# CT.net
KiCad netlist of a schematic drawn in Altium Designer
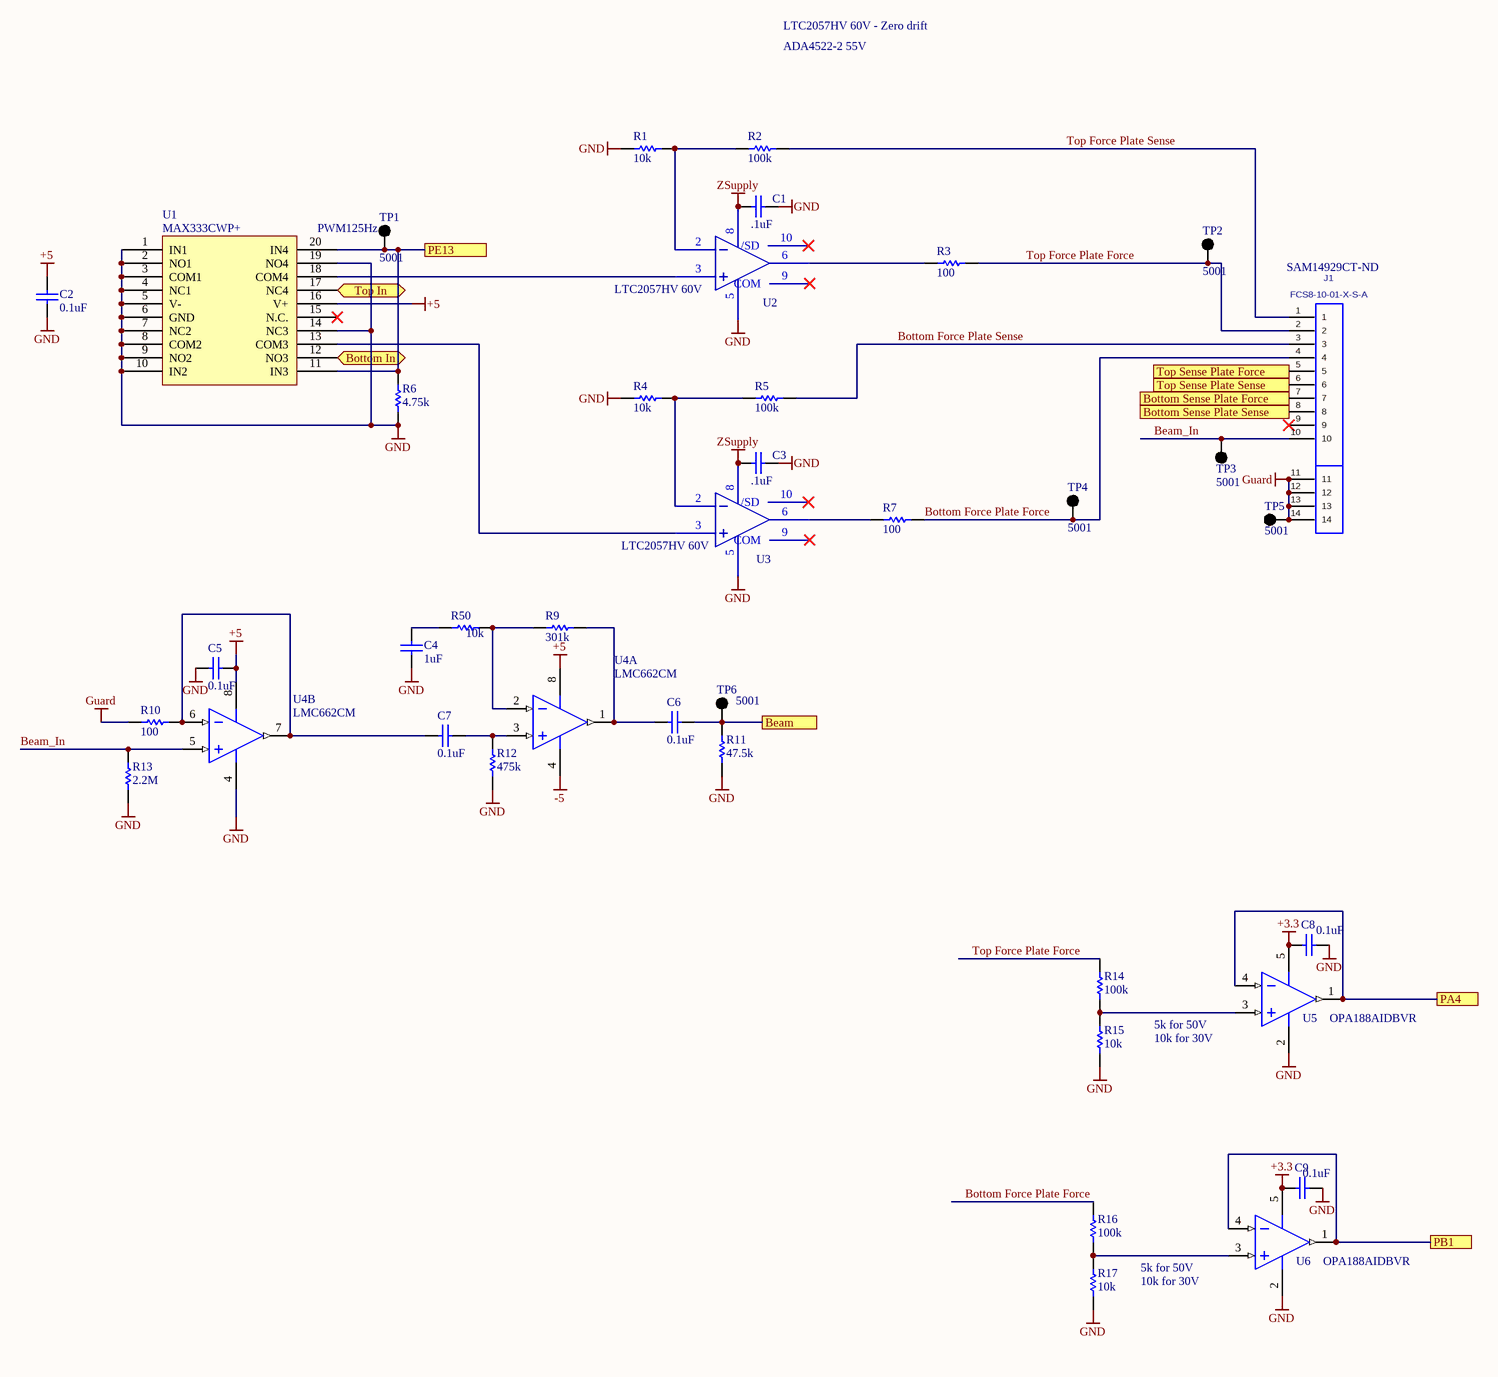
[diagram p0: CT.SchDoc]

(export (version "E")
  (design (tool "Eeschema 10.0.6"))
  (components
    (comp (ref "C1")
      (value ".1uF")
      (footprint "CAPC0805(2012)75_M")
      (description "0.1µF ±10% 16V Ceramic Capacitor X7R 0805 (2012 Metric)")
      (fields
        (field (name "MANUFACTURER") "Yageo")
        (field (name "MANUFACTURER PART NUMBER") "CC0805KRX7R7BB104")
      )
      (libsource (lib "Altium Content Vault") (part "CMP-1036-01414-1"))
    )
    (comp (ref "C2")
      (value "0.1uF")
      (footprint "CAPC0402(1005)60_L")
      (description "CAP CER 0.1UF 10V X7R 0402")
      (fields
        (field (name "MANUFACTURER") "Murata Electronics North America")
        (field (name "MANUFACTURER PART NUMBER") "GRM155R71A104KA01D")
      )
      (libsource (lib "Altium Content Vault") (part "CMP-1034-00252-1"))
    )
    (comp (ref "C3")
      (value ".1uF")
      (footprint "CAPC0805(2012)75_M")
      (description "0.1µF ±10% 16V Ceramic Capacitor X7R 0805 (2012 Metric)")
      (fields
        (field (name "MANUFACTURER") "Yageo")
        (field (name "MANUFACTURER PART NUMBER") "CC0805KRX7R7BB104")
      )
      (libsource (lib "Altium Content Vault") (part "CMP-1036-01414-1"))
    )
    (comp (ref "C4")
      (value "1uF")
      (footprint "CAPC0402(1005)60_L")
      (description "1µF ±10% 16V Ceramic Capacitor X5R 0402 (1005 Metric)")
      (fields
        (field (name "MANUFACTURER") "Samsung")
        (field (name "MANUFACTURER PART NUMBER") "CL05A105KO5NNNC")
      )
      (libsource (lib "Altium Content Vault") (part "CMP-1034-00252-1"))
    )
    (comp (ref "C5")
      (value "0.1uF")
      (footprint "CAPC0402(1005)60_L")
      (description "CAP CER 0.1UF 10V X7R 0402")
      (fields
        (field (name "MANUFACTURER") "Murata Electronics North America")
        (field (name "MANUFACTURER PART NUMBER") "GRM155R71A104KA01D")
      )
      (libsource (lib "Altium Content Vault") (part "CMP-1034-00252-1"))
    )
    (comp (ref "C6")
      (value "0.1uF")
      (footprint "CAPC0402(1005)60_L")
      (description "CAP CER 0.1UF 10V X7R 0402")
      (fields
        (field (name "MANUFACTURER") "Murata Electronics North America")
        (field (name "MANUFACTURER PART NUMBER") "GRM155R71A104KA01D")
      )
      (libsource (lib "Altium Content Vault") (part "CMP-1034-00252-1"))
    )
    (comp (ref "C7")
      (value "0.1uF")
      (footprint "CAPC0402(1005)60_L")
      (description "CAP CER 0.1UF 10V X7R 0402")
      (fields
        (field (name "MANUFACTURER") "Murata Electronics North America")
        (field (name "MANUFACTURER PART NUMBER") "GRM155R71A104KA01D")
      )
      (libsource (lib "Altium Content Vault") (part "CMP-1034-00252-1"))
    )
    (comp (ref "C8")
      (value "0.1uF")
      (footprint "CAPC0402(1005)60_L")
      (description "CAP CER 0.1UF 10V X7R 0402")
      (fields
        (field (name "MANUFACTURER") "Murata Electronics North America")
        (field (name "MANUFACTURER PART NUMBER") "GRM155R71A104KA01D")
      )
      (libsource (lib "Altium Content Vault") (part "CMP-1034-00252-1"))
    )
    (comp (ref "C9")
      (value "0.1uF")
      (footprint "CAPC0402(1005)60_L")
      (description "CAP CER 0.1UF 10V X7R 0402")
      (fields
        (field (name "MANUFACTURER") "Murata Electronics North America")
        (field (name "MANUFACTURER PART NUMBER") "GRM155R71A104KA01D")
      )
      (libsource (lib "Altium Content Vault") (part "CMP-1034-00252-1"))
    )
    (comp (ref "J1")
      (value "FCS8-10-01-X-S-A")
      (footprint "FCS8-10-01-X-S-A")
      (description "FCS8 Socket Assembly, 20-Pins, w/ Alignment Pins")
      (fields
        (field (name "SUPPLIER PART NUMBER 1") "SAM14929CT-ND")
        (field (name "MANUFACTURER") "Samtec")
        (field (name "MANUFACTURER PART NUMBER") "FCS8-10-01-L-S-A-TR")
        (field (name "CREATED") "31 NOV 2013 - WENDY XIN")
      )
      (libsource (lib "FCS8-10-01-X-S-A") (part "FCS8-10-01-X-S-A"))
    )
    (comp (ref "R1")
      (value "10k")
      (footprint "RESC0402(1005)_M")
      (description "10k 0.063W 1% 0402 (1005 Metric)  SMD")
      (fields
        (field (name "MANUFACTURER") "Panasonic")
        (field (name "MANUFACTURER PART NUMBER") "ERJ-2RKF1002X")
      )
      (libsource (lib "Altium Content Vault") (part "RES"))
    )
    (comp (ref "R2")
      (value "100k")
      (footprint "RESC0402(1005)_M")
      (description "100k 0.063W 1% 0402 (1005 Metric)  SMD")
      (fields
        (field (name "MANUFACTURER") "Panasonic")
        (field (name "MANUFACTURER PART NUMBER") "ERJ-2RKF1003X")
      )
      (libsource (lib "Altium Content Vault") (part "RES"))
    )
    (comp (ref "R3")
      (value "100")
      (footprint "RESC0402(1005)_N")
      (description "RES SMD 100 OHM 1% 1/16W 0402")
      (fields (field (name "TOLERANCE") "1 %") (field (name "POWER") "0.063 W"))
      (libsource (lib "Altium Content Vault") (part "RES"))
    )
    (comp (ref "R4")
      (value "10k")
      (footprint "RESC0402(1005)_M")
      (description "10k 0.063W 1% 0402 (1005 Metric)  SMD")
      (fields
        (field (name "MANUFACTURER") "Panasonic")
        (field (name "MANUFACTURER PART NUMBER") "ERJ-2RKF1002X")
      )
      (libsource (lib "Altium Content Vault") (part "RES"))
    )
    (comp (ref "R5")
      (value "100k")
      (footprint "RESC0402(1005)_M")
      (description "100k 0.063W 1% 0402 (1005 Metric)  SMD")
      (fields
        (field (name "MANUFACTURER") "Panasonic")
        (field (name "MANUFACTURER PART NUMBER") "ERJ-2RKF1003X")
      )
      (libsource (lib "Altium Content Vault") (part "RES"))
    )
    (comp (ref "R6")
      (value "4.75k")
      (footprint "RESC1005X40X25ML05T05")
      (description "Chip Resistor, 4.75 KOhm, +/- 1%, 100 mW, -55 to 155 degC, 0402 (1005 Metric), RoHS, Tape and Reel")
      (fields (field (name "PARTNUMBER") "ERJ-2RKF4751X") (field (name "MANUFACTURER") "Basic Passives"))
      (libsource (lib "Altium Content Vault") (part "RES-2"))
    )
    (comp (ref "R7")
      (value "100")
      (footprint "RESC0402(1005)_N")
      (description "RES SMD 100 OHM 1% 1/16W 0402")
      (fields (field (name "TOLERANCE") "1 %") (field (name "POWER") "0.063 W"))
      (libsource (lib "Altium Content Vault") (part "RES"))
    )
    (comp (ref "R9")
      (value "301k")
      (footprint "RESC0402(1005)_M")
      (description "RES SMD 301K OHM 1% 1/10W 0402")
      (fields
        (field (name "MANUFACTURER") "Panasonic")
        (field (name "MANUFACTURER PART NUMBER") "ERJ-2RKF3013X")
      )
      (libsource (lib "Altium Content Vault") (part "CMP-1011-00463-1"))
    )
    (comp (ref "R10")
      (value "100")
      (footprint "RESC0402(1005)_M")
      (description "6M34 0.063W 1% 0402 (1005 Metric)  SMD")
      (fields
        (field (name "MANUFACTURER") "Panasonic")
        (field (name "MANUFACTURER PART NUMBER") "ERJ-2RKF1000X")
      )
      (libsource (lib "Altium Content Vault") (part "RES"))
    )
    (comp (ref "R11")
      (value "47.5k")
      (footprint "RESC1005X40X25NL05T05")
      (description "RESISTOR, 0402, 47K5 1%, 0.1W")
      (fields (field (name "PART NUMBER") "ERJ-2RKF4752X") (field (name "MANUFACTURER") "Panasonic"))
      (libsource (lib "Altium Content Vault") (part "RES"))
    )
    (comp (ref "R12")
      (value "475k")
      (footprint "RESC1005X40X25LL05T05")
      (description "Resistor 0402 Case 475k 1% 0.1W 100ppm/C")
      (fields (field (name "PART NUMBER") "ERJ-2RKF4753X") (field (name "MANUFACTURER") "Panasonic"))
      (libsource (lib "Altium Content Vault") (part "RES"))
    )
    (comp (ref "R13")
      (value "2.2M")
      (footprint "RESC1005X40X25ML05T10")
      (description "RESISTOR, 0402 2M2 1%, REEL 10000")
      (fields (field (name "PART NUMBER") "RC0402FR-072M2L") (field (name "MANUFACTURER") "Yageo / Phycomp"))
      (libsource (lib "Altium Content Vault") (part "RES"))
    )
    (comp (ref "R14")
      (value "100k")
      (footprint "RESC0402(1005)_M")
      (description "100k 0.063W 1% 0402 (1005 Metric)  SMD")
      (fields
        (field (name "MANUFACTURER") "Panasonic")
        (field (name "MANUFACTURER PART NUMBER") "ERJ-2RKF1003X")
      )
      (libsource (lib "Altium Content Vault") (part "RES"))
    )
    (comp (ref "R15")
      (value "10k")
      (footprint "RESC0402(1005)_M")
      (description "10k 0.063W 1% 0402 (1005 Metric)  SMD")
      (fields
        (field (name "MANUFACTURER") "Panasonic")
        (field (name "MANUFACTURER PART NUMBER") "ERJ-2RKF1002X")
      )
      (libsource (lib "Altium Content Vault") (part "RES"))
    )
    (comp (ref "R16")
      (value "100k")
      (footprint "RESC0402(1005)_M")
      (description "100k 0.063W 1% 0402 (1005 Metric)  SMD")
      (fields
        (field (name "MANUFACTURER") "Panasonic")
        (field (name "MANUFACTURER PART NUMBER") "ERJ-2RKF1003X")
      )
      (libsource (lib "Altium Content Vault") (part "RES"))
    )
    (comp (ref "R17")
      (value "10k")
      (footprint "RESC0402(1005)_M")
      (description "10k 0.063W 1% 0402 (1005 Metric)  SMD")
      (fields
        (field (name "MANUFACTURER") "Panasonic")
        (field (name "MANUFACTURER PART NUMBER") "ERJ-2RKF1002X")
      )
      (libsource (lib "Altium Content Vault") (part "RES"))
    )
    (comp (ref "R50")
      (value "10k")
      (footprint "RESC0402(1005)_M")
      (description "10k 0.063W 1% 0402 (1005 Metric)  SMD")
      (fields
        (field (name "MANUFACTURER") "Panasonic")
        (field (name "MANUFACTURER PART NUMBER") "ERJ-2RKF1002X")
      )
      (libsource (lib "Altium Content Vault") (part "RES"))
    )
    (comp (ref "TP1")
      (value "5001")
      (footprint "KSTN-5001")
      (description "Test Point, Black, 1-Pin THD, RoHS, Bulk")
      (fields (field (name "MANUFACTURER") "Keystone"))
      (libsource (lib "Altium Content Vault") (part "KSTN-TP-5001"))
    )
    (comp (ref "TP2")
      (value "5001")
      (footprint "KSTN-5001")
      (description "Test Point, Black, 1-Pin THD, RoHS, Bulk")
      (fields (field (name "MANUFACTURER") "Keystone"))
      (libsource (lib "Altium Content Vault") (part "KSTN-TP-5001"))
    )
    (comp (ref "TP3")
      (value "5001")
      (footprint "KSTN-5001")
      (description "Test Point, Black, 1-Pin THD, RoHS, Bulk")
      (fields (field (name "MANUFACTURER") "Keystone"))
      (libsource (lib "Altium Content Vault") (part "KSTN-TP-5001"))
    )
    (comp (ref "TP4")
      (value "5001")
      (footprint "KSTN-5001")
      (description "Test Point, Black, 1-Pin THD, RoHS, Bulk")
      (fields (field (name "MANUFACTURER") "Keystone"))
      (libsource (lib "Altium Content Vault") (part "KSTN-TP-5001"))
    )
    (comp (ref "TP5")
      (value "5001")
      (footprint "KSTN-5001")
      (description "Test Point, Black, 1-Pin THD, RoHS, Bulk")
      (fields (field (name "MANUFACTURER") "Keystone"))
      (libsource (lib "Altium Content Vault") (part "KSTN-TP-5001"))
    )
    (comp (ref "TP6")
      (value "5001")
      (footprint "KSTN-5001")
      (description "Test Point, Black, 1-Pin THD, RoHS, Bulk")
      (fields (field (name "MANUFACTURER") "Keystone"))
      (libsource (lib "Altium Content Vault") (part "KSTN-TP-5001"))
    )
    (comp (ref "U1")
      (value "MAX333CWP+")
      (footprint "TSOP65P640X90-20N")
      (description "IC SWITCH QUAD SPDT 20TSSOP")
      (fields (field (name "MANUFACTURER") "Maxim") (field (name "MANUFACTURER PART NUMBER") "MAX333AEUP+"))
      (libsource (lib "ZLS_Schematic_lib") (part "MAX333CWP+"))
    )
    (comp (ref "U2")
      (value "LTC2057HV 60V")
      (description "IC OPAMP ZRO-DRFT 1.5MHZ 10MSOP")
      (fields
        (field (name "MANUFACTURER") "Analog Devices / Linear Technology")
        (field (name "MANUFACTURER PART NUMBER") "LTC2057HVHMS#PBF")
      )
      (libsource (lib "ZLS_Schematic_lib") (part "LTC2057HV 60V"))
    )
    (comp (ref "U3")
      (value "LTC2057HV 60V")
      (description "IC OPAMP ZRO-DRFT 1.5MHZ 10MSOP")
      (fields
        (field (name "MANUFACTURER") "Analog Devices / Linear Technology")
        (field (name "MANUFACTURER PART NUMBER") "LTC2057HVHMS#PBF")
      )
      (libsource (lib "ZLS_Schematic_lib") (part "LTC2057HV 60V"))
    )
    (comp (ref "U4")
      (value "LMC662CM")
      (footprint "D0008A_M")
      (description "CMOS Dual Operational Amplifier, 8-pin Narrow SOIC")
      (fields (field (name "MANUFACTURER") "Texas Instruments"))
      (libsource (lib "Altium Content Vault") (part "AMP-OPA-LF353-8"))
    )
    (comp (ref "U5")
      (value "OPA188AIDBVR")
      (footprint "DBV0005A_M")
      (fields (field (name "MANUFACTURER") "Texas Instruments"))
      (libsource (lib "Altium Content Vault") (part "CMP-0809-00005-2"))
    )
    (comp (ref "U6")
      (value "OPA188AIDBVR")
      (footprint "DBV0005A_M")
      (fields (field (name "MANUFACTURER") "Texas Instruments"))
      (libsource (lib "Altium Content Vault") (part "CMP-0809-00005-2"))
    )
  )
  (nets
    (net (code "1") (name "+3.3") (class "Default")
      (node (ref "C8") (pin "2") (pinfunction "2_2") (pintype "passive"))
      (node (ref "C9") (pin "2") (pinfunction "2_2") (pintype "passive"))
      (node (ref "U5") (pin "5") (pinfunction "V+_5") (pintype "power_in"))
      (node (ref "U6") (pin "5") (pinfunction "V+_5") (pintype "power_in"))
    )
    (net (code "2") (name "+5") (class "Default")
      (node (ref "C2") (pin "2") (pinfunction "2_2") (pintype "passive"))
      (node (ref "C5") (pin "2") (pinfunction "2_2") (pintype "passive"))
      (node (ref "U1") (pin "16") (pinfunction "V+_16") (pintype "power_in"))
      (node (ref "U4") (pin "8") (pinfunction "V+_8") (pintype "power_in"))
    )
    (net (code "3") (name "-5") (class "Default")
      (node (ref "U4") (pin "4") (pinfunction "V-_4") (pintype "power_in"))
    )
    (net (code "4") (name "/Beam") (class "Default")
      (node (ref "C6") (pin "2") (pinfunction "2_2") (pintype "passive"))
      (node (ref "R11") (pin "2") (pinfunction "2_2") (pintype "passive"))
      (node (ref "TP6") (pin "1") (pintype "passive"))
    )
    (net (code "5") (name "/Beam_In") (class "Default")
      (node (ref "J1") (pin "10") (pinfunction "10_10") (pintype "passive"))
      (node (ref "R13") (pin "2") (pinfunction "2_2") (pintype "passive"))
      (node (ref "TP3") (pin "1") (pintype "passive"))
      (node (ref "U4") (pin "5") (pinfunction "INB+_5") (pintype "input"))
    )
    (net (code "6") (name "/Bottom Force Plate Force") (class "Default")
      (node (ref "J1") (pin "4") (pinfunction "4_4") (pintype "passive"))
      (node (ref "R16") (pin "2") (pinfunction "2_2") (pintype "passive"))
      (node (ref "R7") (pin "2") (pinfunction "2_2") (pintype "passive"))
      (node (ref "TP4") (pin "1") (pintype "passive"))
    )
    (net (code "7") (name "/Bottom Force Plate Sense") (class "Default")
      (node (ref "J1") (pin "3") (pinfunction "3_3") (pintype "passive"))
      (node (ref "R5") (pin "2") (pinfunction "2_2") (pintype "passive"))
    )
    (net (code "8") (name "/Bottom In") (class "Default")
      (node (ref "U1") (pin "12") (pinfunction "NO3_12") (pintype "passive"))
    )
    (net (code "9") (name "/Bottom Sense Plate Force") (class "Default")
      (node (ref "J1") (pin "7") (pinfunction "7_7") (pintype "passive"))
    )
    (net (code "10") (name "/Bottom Sense Plate Sense") (class "Default")
      (node (ref "J1") (pin "8") (pinfunction "8_8") (pintype "passive"))
    )
    (net (code "11") (name "/PA4") (class "Default")
      (node (ref "U5") (pin "1") (pinfunction "OUT_1") (pintype "output"))
      (node (ref "U5") (pin "4") (pinfunction "IN-_4") (pintype "input"))
    )
    (net (code "12") (name "/PB1") (class "Default")
      (node (ref "U6") (pin "1") (pinfunction "OUT_1") (pintype "output"))
      (node (ref "U6") (pin "4") (pinfunction "IN-_4") (pintype "input"))
    )
    (net (code "13") (name "/PE13") (class "Default")
      (node (ref "R6") (pin "2") (pinfunction "2_2") (pintype "passive"))
      (node (ref "TP1") (pin "1") (pintype "passive"))
      (node (ref "U1") (pin "11") (pinfunction "IN3_11") (pintype "passive"))
      (node (ref "U1") (pin "20") (pinfunction "IN4_20") (pintype "passive"))
    )
    (net (code "14") (name "/Top Force Plate Force") (class "Default")
      (node (ref "J1") (pin "2") (pinfunction "2_2") (pintype "passive"))
      (node (ref "R14") (pin "2") (pinfunction "2_2") (pintype "passive"))
      (node (ref "R3") (pin "2") (pinfunction "2_2") (pintype "passive"))
      (node (ref "TP2") (pin "1") (pintype "passive"))
    )
    (net (code "15") (name "/Top Force Plate Sense") (class "Default")
      (node (ref "J1") (pin "1") (pinfunction "1_1") (pintype "passive"))
      (node (ref "R2") (pin "2") (pinfunction "2_2") (pintype "passive"))
    )
    (net (code "16") (name "/Top In") (class "Default")
      (node (ref "U1") (pin "17") (pinfunction "NC4_17") (pintype "passive"))
    )
    (net (code "17") (name "/Top Sense Plate Force") (class "Default")
      (node (ref "J1") (pin "5") (pinfunction "5_5") (pintype "passive"))
    )
    (net (code "18") (name "/Top Sense Plate Sense") (class "Default")
      (node (ref "J1") (pin "6") (pinfunction "6_6") (pintype "passive"))
    )
    (net (code "19") (name "GND") (class "Default")
      (node (ref "C1") (pin "2") (pinfunction "2_2") (pintype "passive"))
      (node (ref "C2") (pin "1") (pinfunction "1_1") (pintype "passive"))
      (node (ref "C3") (pin "2") (pinfunction "2_2") (pintype "passive"))
      (node (ref "C4") (pin "1") (pinfunction "1_1") (pintype "passive"))
      (node (ref "C5") (pin "1") (pinfunction "1_1") (pintype "passive"))
      (node (ref "C8") (pin "1") (pinfunction "1_1") (pintype "passive"))
      (node (ref "C9") (pin "1") (pinfunction "1_1") (pintype "passive"))
      (node (ref "R1") (pin "1") (pinfunction "1_1") (pintype "passive"))
      (node (ref "R11") (pin "1") (pinfunction "1_1") (pintype "passive"))
      (node (ref "R12") (pin "1") (pinfunction "1_1") (pintype "passive"))
      (node (ref "R13") (pin "1") (pinfunction "1_1") (pintype "passive"))
      (node (ref "R15") (pin "1") (pinfunction "1_1") (pintype "passive"))
      (node (ref "R17") (pin "1") (pinfunction "1_1") (pintype "passive"))
      (node (ref "R4") (pin "1") (pinfunction "1_1") (pintype "passive"))
      (node (ref "R6") (pin "1") (pinfunction "1_1") (pintype "passive"))
      (node (ref "U1") (pin "1") (pinfunction "IN1_1") (pintype "passive"))
      (node (ref "U1") (pin "10") (pinfunction "IN2_10") (pintype "passive"))
      (node (ref "U1") (pin "14") (pinfunction "NC3_14") (pintype "passive"))
      (node (ref "U1") (pin "19") (pinfunction "NO4_19") (pintype "passive"))
      (node (ref "U1") (pin "2") (pinfunction "NO1_2") (pintype "passive"))
      (node (ref "U1") (pin "3") (pinfunction "COM1_3") (pintype "passive"))
      (node (ref "U1") (pin "4") (pinfunction "NC1_4") (pintype "passive"))
      (node (ref "U1") (pin "5") (pinfunction "V-_5") (pintype "power_in"))
      (node (ref "U1") (pin "6") (pinfunction "GND_6") (pintype "passive"))
      (node (ref "U1") (pin "7") (pinfunction "NC2_7") (pintype "passive"))
      (node (ref "U1") (pin "8") (pinfunction "COM2_8") (pintype "passive"))
      (node (ref "U1") (pin "9") (pinfunction "NO2_9") (pintype "passive"))
      (node (ref "U2") (pin "5") (pinfunction "V-_5") (pintype "passive"))
      (node (ref "U3") (pin "5") (pinfunction "V-_5") (pintype "passive"))
      (node (ref "U4") (pin "4") (pinfunction "V-_4") (pintype "power_in"))
      (node (ref "U5") (pin "2") (pinfunction "V-_2") (pintype "power_in"))
      (node (ref "U6") (pin "2") (pinfunction "V-_2") (pintype "power_in"))
    )
    (net (code "20") (name "Guard") (class "Default")
      (node (ref "J1") (pin "11") (pinfunction "11_11") (pintype "passive"))
      (node (ref "J1") (pin "12") (pinfunction "12_12") (pintype "passive"))
      (node (ref "J1") (pin "13") (pinfunction "13_13") (pintype "passive"))
      (node (ref "J1") (pin "14") (pinfunction "14_14") (pintype "passive"))
      (node (ref "R10") (pin "1") (pinfunction "1_1") (pintype "passive"))
      (node (ref "TP5") (pin "1") (pintype "passive"))
    )
    (net (code "21") (name "Net-(C4-Pad2)") (class "Default")
      (node (ref "C4") (pin "2") (pinfunction "2_2") (pintype "passive"))
      (node (ref "R50") (pin "1") (pinfunction "1_1") (pintype "passive"))
    )
    (net (code "22") (name "Net-(U1-COM3)") (class "Default")
      (node (ref "U1") (pin "13") (pinfunction "COM3_13") (pintype "passive"))
      (node (ref "U3") (pin "3") (pinfunction "+IN_3") (pintype "passive"))
    )
    (net (code "23") (name "Net-(U1-COM4)") (class "Default")
      (node (ref "U1") (pin "18") (pinfunction "COM4_18") (pintype "passive"))
      (node (ref "U2") (pin "3") (pinfunction "+IN_3") (pintype "passive"))
    )
    (net (code "24") (name "Net-(U2--IN)") (class "Default")
      (node (ref "R1") (pin "2") (pinfunction "2_2") (pintype "passive"))
      (node (ref "R2") (pin "1") (pinfunction "1_1") (pintype "passive"))
      (node (ref "U2") (pin "2") (pinfunction "-IN_2") (pintype "passive"))
    )
    (net (code "25") (name "Net-(U2-OUT)") (class "Default")
      (node (ref "R3") (pin "1") (pinfunction "1_1") (pintype "passive"))
      (node (ref "U2") (pin "6") (pinfunction "OUT_6") (pintype "passive"))
    )
    (net (code "26") (name "Net-(U3--IN)") (class "Default")
      (node (ref "R4") (pin "2") (pinfunction "2_2") (pintype "passive"))
      (node (ref "R5") (pin "1") (pinfunction "1_1") (pintype "passive"))
      (node (ref "U3") (pin "2") (pinfunction "-IN_2") (pintype "passive"))
    )
    (net (code "27") (name "Net-(U3-OUT)") (class "Default")
      (node (ref "R7") (pin "1") (pinfunction "1_1") (pintype "passive"))
      (node (ref "U3") (pin "6") (pinfunction "OUT_6") (pintype "passive"))
    )
    (net (code "28") (name "Net-(U4A-INA+)") (class "Default")
      (node (ref "C7") (pin "2") (pinfunction "2_2") (pintype "passive"))
      (node (ref "R12") (pin "2") (pinfunction "2_2") (pintype "passive"))
      (node (ref "U4") (pin "3") (pinfunction "INA+_3") (pintype "input"))
    )
    (net (code "29") (name "Net-(U4A-INA-)") (class "Default")
      (node (ref "R50") (pin "2") (pinfunction "2_2") (pintype "passive"))
      (node (ref "R9") (pin "2") (pinfunction "2_2") (pintype "passive"))
      (node (ref "U4") (pin "2") (pinfunction "INA-_2") (pintype "input"))
    )
    (net (code "30") (name "Net-(U4A-OUTA)") (class "Default")
      (node (ref "C6") (pin "1") (pinfunction "1_1") (pintype "passive"))
      (node (ref "R9") (pin "1") (pinfunction "1_1") (pintype "passive"))
      (node (ref "U4") (pin "1") (pinfunction "OUTA_1") (pintype "output"))
    )
    (net (code "31") (name "Net-(U4B-INB-)") (class "Default")
      (node (ref "C7") (pin "1") (pinfunction "1_1") (pintype "passive"))
      (node (ref "R10") (pin "2") (pinfunction "2_2") (pintype "passive"))
      (node (ref "U4") (pin "6") (pinfunction "INB-_6") (pintype "input"))
      (node (ref "U4") (pin "7") (pinfunction "OUTB_7") (pintype "output"))
    )
    (net (code "32") (name "Net-(U5-IN+)") (class "Default")
      (node (ref "R14") (pin "1") (pinfunction "1_1") (pintype "passive"))
      (node (ref "R15") (pin "2") (pinfunction "2_2") (pintype "passive"))
      (node (ref "U5") (pin "3") (pinfunction "IN+_3") (pintype "input"))
    )
    (net (code "33") (name "Net-(U6-IN+)") (class "Default")
      (node (ref "R16") (pin "1") (pinfunction "1_1") (pintype "passive"))
      (node (ref "R17") (pin "2") (pinfunction "2_2") (pintype "passive"))
      (node (ref "U6") (pin "3") (pinfunction "IN+_3") (pintype "input"))
    )
    (net (code "34") (name "ZSupply") (class "Default")
      (node (ref "C1") (pin "1") (pinfunction "1_1") (pintype "passive"))
      (node (ref "C3") (pin "1") (pinfunction "1_1") (pintype "passive"))
      (node (ref "U2") (pin "8") (pinfunction "V+_8") (pintype "passive"))
      (node (ref "U3") (pin "8") (pinfunction "V+_8") (pintype "passive"))
    )
    (net (code "35") (name "unconnected-(J1-Pad9)") (class "Default")
      (node (ref "J1") (pin "9") (pinfunction "9_9") (pintype "passive+no_connect"))
    )
    (net (code "36") (name "unconnected-(U1-N.C.-Pad15)") (class "Default")
      (node (ref "U1") (pin "15") (pinfunction "N.C._15") (pintype "passive+no_connect"))
    )
    (net (code "37") (name "unconnected-(U2-COM-Pad9)") (class "Default")
      (node (ref "U2") (pin "9") (pinfunction "COM_9") (pintype "passive+no_connect"))
    )
    (net (code "38") (name "unconnected-(U2-N.C.-Pad7)") (class "Default")
      (node (ref "U2") (pin "7") (pinfunction "N.C._7") (pintype "passive"))
    )
    (net (code "39") (name "unconnected-(U2-{slash}SD-Pad10)") (class "Default")
      (node (ref "U2") (pin "10") (pinfunction "/SD_10") (pintype "passive+no_connect"))
    )
    (net (code "40") (name "unconnected-(U3-COM-Pad9)") (class "Default")
      (node (ref "U3") (pin "9") (pinfunction "COM_9") (pintype "passive+no_connect"))
    )
    (net (code "41") (name "unconnected-(U3-N.C.-Pad7)") (class "Default")
      (node (ref "U3") (pin "7") (pinfunction "N.C._7") (pintype "passive"))
    )
    (net (code "42") (name "unconnected-(U3-{slash}SD-Pad10)") (class "Default")
      (node (ref "U3") (pin "10") (pinfunction "/SD_10") (pintype "passive+no_connect"))
    )
  )
)
